# 02_POWER.net
KiCad netlist of a schematic drawn in Altium Designer
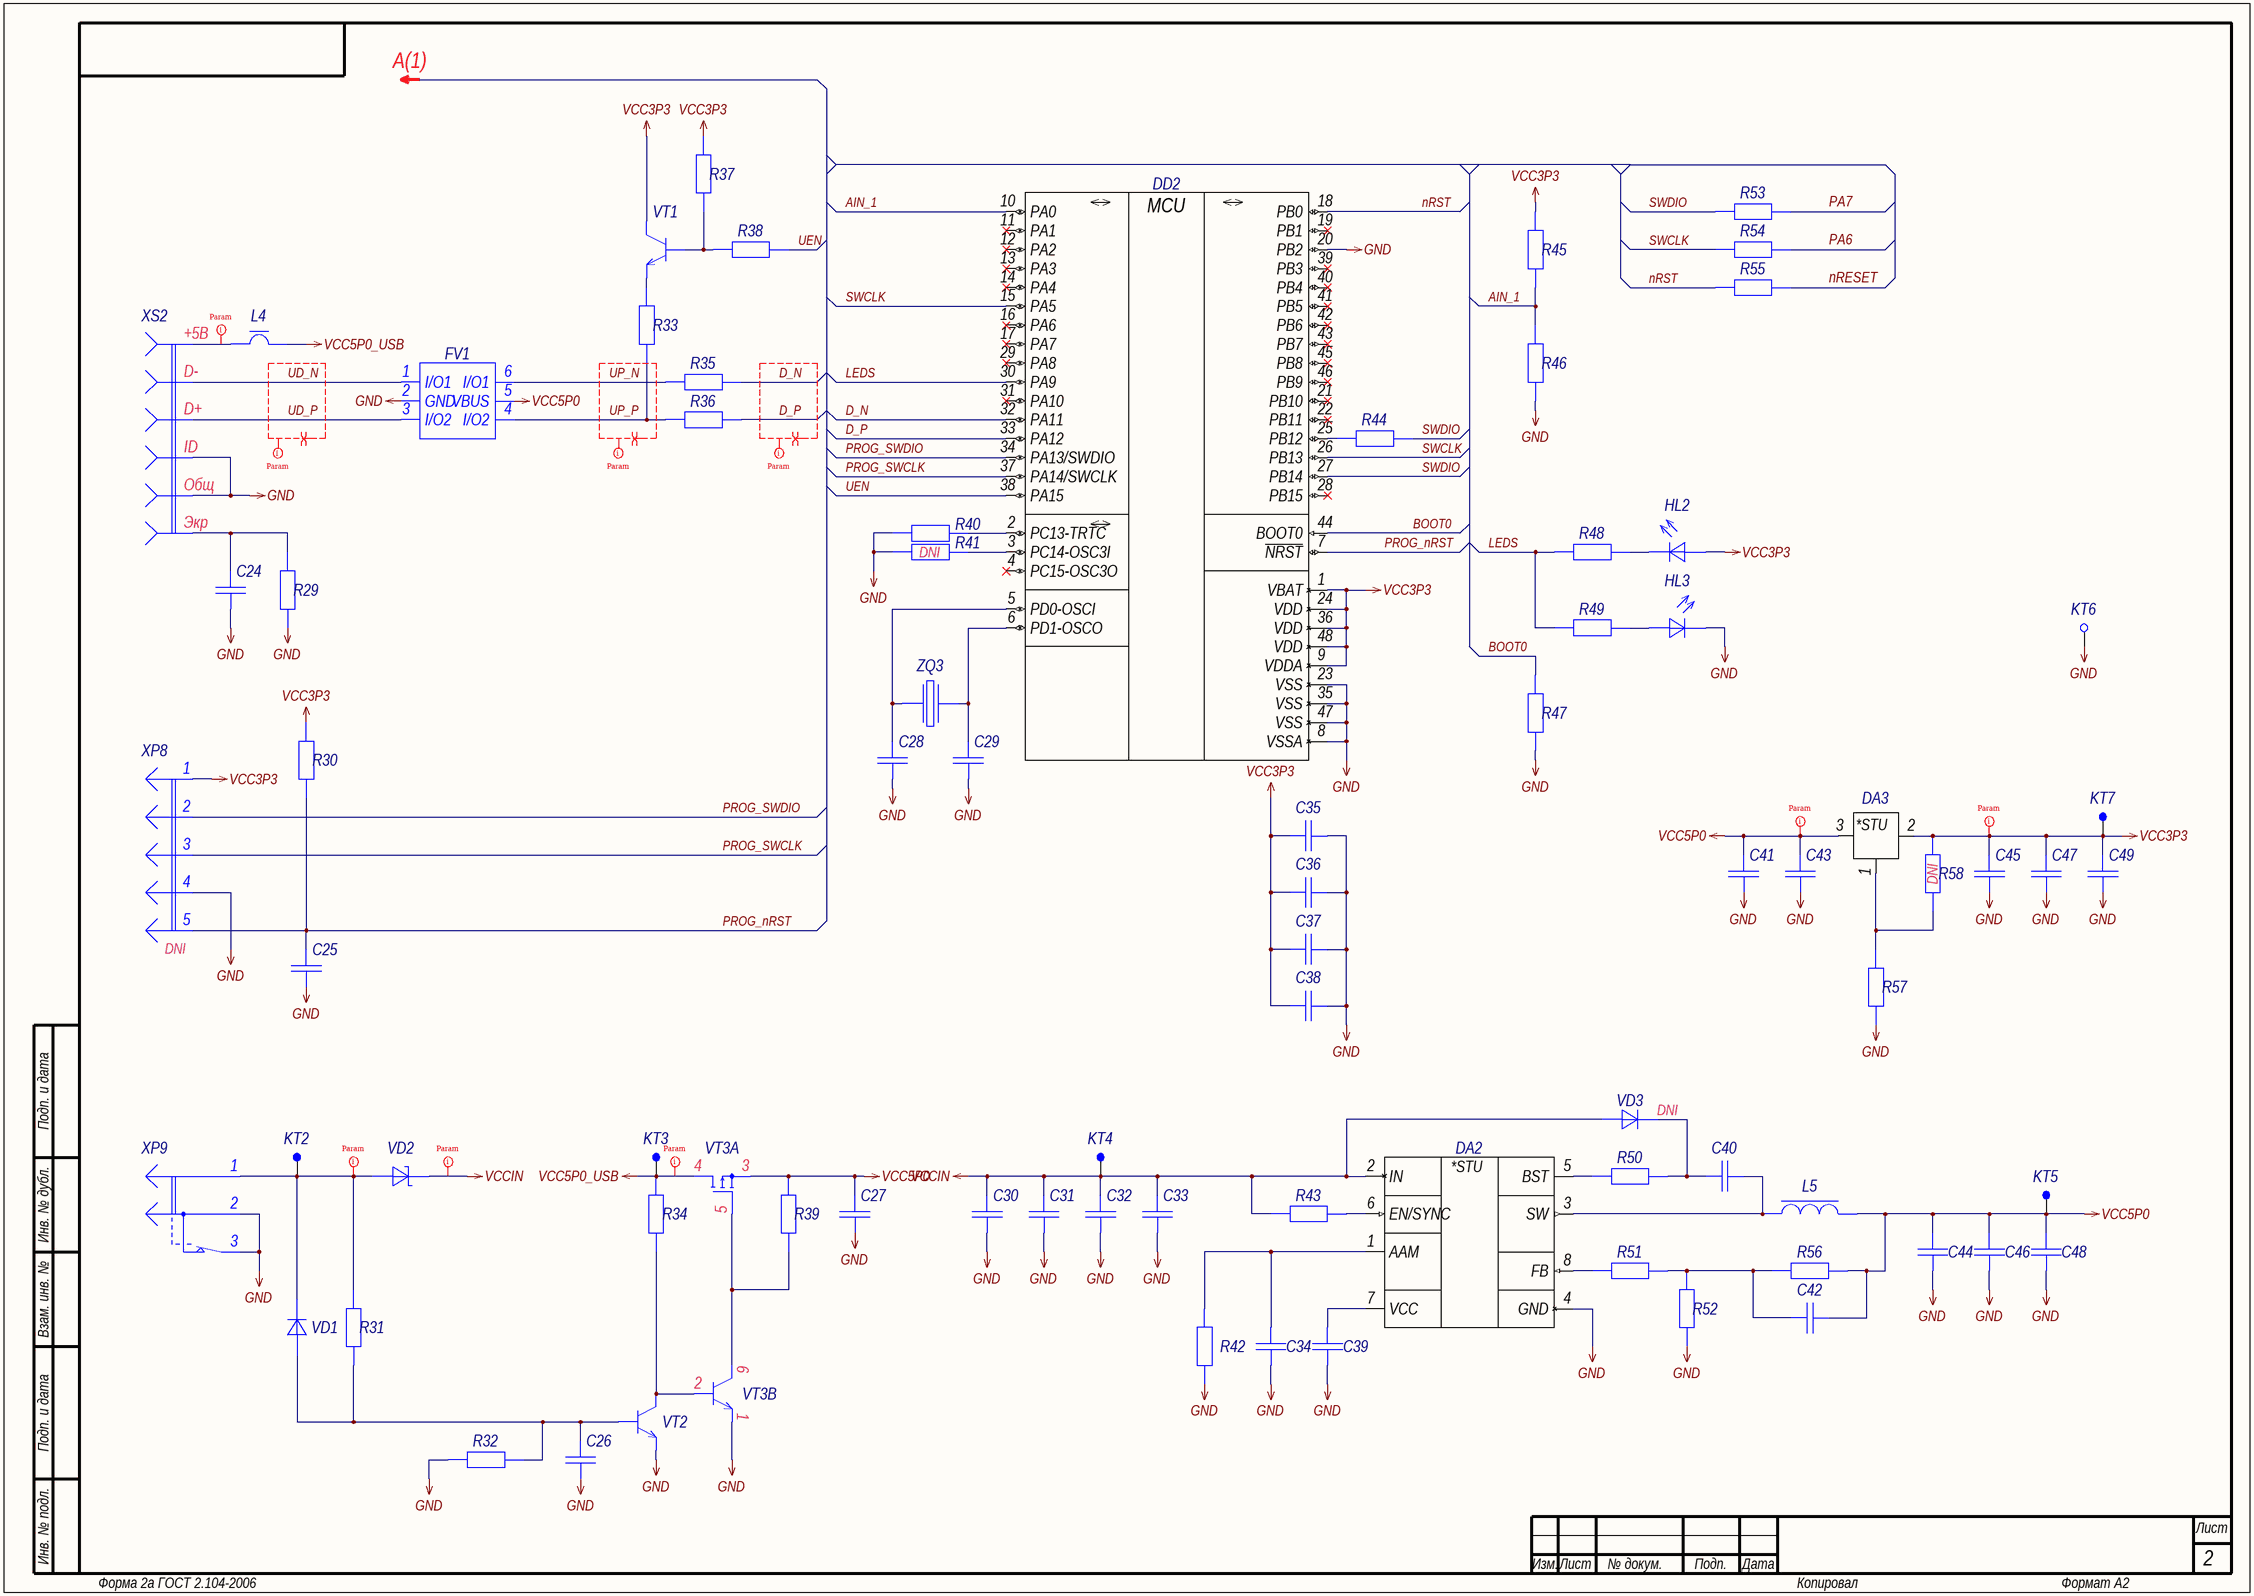
[diagram p0: 02_POWER.SchDoc]

(export (version "E")
  (design (tool "Eeschema 10.0.6"))
  (components
    (comp (ref "C24")
      (value "Capacitor")
      (footprint "C0603_L")
      (fields
        (field (name "PART NUMBER") "GRM188R72A104KA35D")
        (field (name "VOLTAGE") "100V")
        (field (name "TOLERANCE") "±10%")
        (field (name "PUBLISHER") "Andrew Danich")
      )
      (libsource (lib "ADLib") (part "Capacitor"))
    )
    (comp (ref "C25")
      (value "Capacitor")
      (footprint "C0603_L")
      (fields
        (field (name "PART NUMBER") "GRM188R72A104KA35D")
        (field (name "VOLTAGE") "100V")
        (field (name "TOLERANCE") "±10%")
        (field (name "PUBLISHER") "Andrew Danich")
      )
      (libsource (lib "ADLib") (part "Capacitor"))
    )
    (comp (ref "C26")
      (value "Capacitor")
      (footprint "C0603_L")
      (fields
        (field (name "PART NUMBER") "GRM188R72A104KA35D")
        (field (name "VOLTAGE") "100V")
        (field (name "TOLERANCE") "±10%")
        (field (name "PUBLISHER") "Andrew Danich")
      )
      (libsource (lib "ADLib") (part "Capacitor"))
    )
    (comp (ref "C27")
      (value "Capacitor")
      (footprint "C0805_L")
      (fields
        (field (name "PART NUMBER") "GRM21BR60J226ME39L")
        (field (name "VOLTAGE") "6.3V")
        (field (name "TOLERANCE") "±20%")
        (field (name "PUBLISHER") "Andrew Danich")
      )
      (libsource (lib "ADLib") (part "Capacitor"))
    )
    (comp (ref "C28")
      (value "Capacitor")
      (footprint "C0603_L")
      (fields
        (field (name "PART NUMBER") "GCM1885C1H150JA16D")
        (field (name "VOLTAGE") "50V")
        (field (name "TOLERANCE") "±5%")
        (field (name "PUBLISHER") "Andrew Danich")
      )
      (libsource (lib "ADLib") (part "Capacitor"))
    )
    (comp (ref "C29")
      (value "Capacitor")
      (footprint "C0603_L")
      (fields
        (field (name "PART NUMBER") "GCM1885C1H150JA16D")
        (field (name "VOLTAGE") "50V")
        (field (name "TOLERANCE") "±5%")
        (field (name "PUBLISHER") "Andrew Danich")
      )
      (libsource (lib "ADLib") (part "Capacitor"))
    )
    (comp (ref "C30")
      (value "Capacitor")
      (footprint "C1206_L")
      (fields
        (field (name "PART NUMBER") "GRM31CR71A226KE15L")
        (field (name "VOLTAGE") "10V")
        (field (name "TOLERANCE") "±10%")
        (field (name "PUBLISHER") "Andrew Danich")
      )
      (libsource (lib "ADLib") (part "Capacitor"))
    )
    (comp (ref "C31")
      (value "Capacitor")
      (footprint "C1206_L")
      (fields
        (field (name "PART NUMBER") "GRM31CR71A226KE15L")
        (field (name "VOLTAGE") "10V")
        (field (name "TOLERANCE") "±10%")
        (field (name "PUBLISHER") "Andrew Danich")
      )
      (libsource (lib "ADLib") (part "Capacitor"))
    )
    (comp (ref "C32")
      (value "Capacitor")
      (footprint "C1206_L")
      (fields
        (field (name "PART NUMBER") "GRM31CR71A226KE15L")
        (field (name "VOLTAGE") "10V")
        (field (name "TOLERANCE") "±10%")
        (field (name "PUBLISHER") "Andrew Danich")
      )
      (libsource (lib "ADLib") (part "Capacitor"))
    )
    (comp (ref "C33")
      (value "Capacitor")
      (footprint "C0603_L")
      (fields
        (field (name "PART NUMBER") "GRM188R72A104KA35D")
        (field (name "VOLTAGE") "100V")
        (field (name "TOLERANCE") "±10%")
        (field (name "PUBLISHER") "Andrew Danich")
      )
      (libsource (lib "ADLib") (part "Capacitor"))
    )
    (comp (ref "C34")
      (value "Capacitor")
      (footprint "C0603_L")
      (fields
        (field (name "PART NUMBER") "GRM1885C2A102JA01D")
        (field (name "VOLTAGE") "100V")
        (field (name "TOLERANCE") "±5%")
        (field (name "PUBLISHER") "Andrew Danich")
      )
      (libsource (lib "ADLib") (part "Capacitor"))
    )
    (comp (ref "C35")
      (value "Capacitor")
      (footprint "C0603_L")
      (fields
        (field (name "PART NUMBER") "GRM188R72A104KA35D")
        (field (name "VOLTAGE") "100V")
        (field (name "TOLERANCE") "±10%")
        (field (name "PUBLISHER") "Andrew Danich")
      )
      (libsource (lib "ADLib") (part "Capacitor"))
    )
    (comp (ref "C36")
      (value "Capacitor")
      (footprint "C0603_L")
      (fields
        (field (name "PART NUMBER") "GRM188R72A104KA35D")
        (field (name "VOLTAGE") "100V")
        (field (name "TOLERANCE") "±10%")
        (field (name "PUBLISHER") "Andrew Danich")
      )
      (libsource (lib "ADLib") (part "Capacitor"))
    )
    (comp (ref "C37")
      (value "Capacitor")
      (footprint "C0603_L")
      (fields
        (field (name "PART NUMBER") "GRM188R72A104KA35D")
        (field (name "VOLTAGE") "100V")
        (field (name "TOLERANCE") "±10%")
        (field (name "PUBLISHER") "Andrew Danich")
      )
      (libsource (lib "ADLib") (part "Capacitor"))
    )
    (comp (ref "C38")
      (value "Capacitor")
      (footprint "C0603_L")
      (fields
        (field (name "PART NUMBER") "GRM188R72A104KA35D")
        (field (name "VOLTAGE") "100V")
        (field (name "TOLERANCE") "±10%")
        (field (name "PUBLISHER") "Andrew Danich")
      )
      (libsource (lib "ADLib") (part "Capacitor"))
    )
    (comp (ref "C39")
      (value "Capacitor")
      (footprint "C0603_L")
      (fields
        (field (name "PART NUMBER") "GRM188R72A104KA35D")
        (field (name "VOLTAGE") "100V")
        (field (name "TOLERANCE") "±10%")
        (field (name "PUBLISHER") "Andrew Danich")
      )
      (libsource (lib "ADLib") (part "Capacitor"))
    )
    (comp (ref "C40")
      (value "Capacitor")
      (footprint "C0603_L")
      (fields
        (field (name "PART NUMBER") "GRM188R72A104KA35D")
        (field (name "VOLTAGE") "100V")
        (field (name "TOLERANCE") "±10%")
        (field (name "PUBLISHER") "Andrew Danich")
      )
      (libsource (lib "ADLib") (part "Capacitor"))
    )
    (comp (ref "C41")
      (value "Capacitor")
      (footprint "C0805_L")
      (fields
        (field (name "PART NUMBER") "GRM21BR60J226ME39L")
        (field (name "VOLTAGE") "6.3V")
        (field (name "TOLERANCE") "±20%")
        (field (name "PUBLISHER") "Andrew Danich")
      )
      (libsource (lib "ADLib") (part "Capacitor"))
    )
    (comp (ref "C42")
      (value "Capacitor")
      (footprint "C0603_L")
      (fields
        (field (name "PART NUMBER") "GRM1885C1H330JA01D")
        (field (name "VOLTAGE") "50V")
        (field (name "TOLERANCE") "±5%")
        (field (name "PUBLISHER") "Andrew Danich")
      )
      (libsource (lib "ADLib") (part "Capacitor"))
    )
    (comp (ref "C43")
      (value "Capacitor")
      (footprint "C0603_L")
      (fields
        (field (name "PART NUMBER") "GRM188R72A104KA35D")
        (field (name "VOLTAGE") "100V")
        (field (name "TOLERANCE") "±10%")
        (field (name "PUBLISHER") "Andrew Danich")
      )
      (libsource (lib "ADLib") (part "Capacitor"))
    )
    (comp (ref "C44")
      (value "Capacitor")
      (footprint "C0805_L")
      (fields
        (field (name "PART NUMBER") "GRM21BR60J226ME39L")
        (field (name "VOLTAGE") "6.3V")
        (field (name "TOLERANCE") "±20%")
        (field (name "PUBLISHER") "Andrew Danich")
      )
      (libsource (lib "ADLib") (part "Capacitor"))
    )
    (comp (ref "C45")
      (value "Capacitor")
      (footprint "C0603_L")
      (fields
        (field (name "PART NUMBER") "GRM188R72A104KA35D")
        (field (name "VOLTAGE") "100V")
        (field (name "TOLERANCE") "±10%")
        (field (name "PUBLISHER") "Andrew Danich")
      )
      (libsource (lib "ADLib") (part "Capacitor"))
    )
    (comp (ref "C46")
      (value "Capacitor")
      (footprint "C0805_L")
      (fields
        (field (name "PART NUMBER") "GRM21BR60J226ME39L")
        (field (name "VOLTAGE") "6.3V")
        (field (name "TOLERANCE") "±20%")
        (field (name "PUBLISHER") "Andrew Danich")
      )
      (libsource (lib "ADLib") (part "Capacitor"))
    )
    (comp (ref "C47")
      (value "Capacitor")
      (footprint "C0805_L")
      (fields
        (field (name "PART NUMBER") "GRM21BR60J226ME39L")
        (field (name "VOLTAGE") "6.3V")
        (field (name "TOLERANCE") "±20%")
        (field (name "PUBLISHER") "Andrew Danich")
      )
      (libsource (lib "ADLib") (part "Capacitor"))
    )
    (comp (ref "C48")
      (value "Capacitor")
      (footprint "C0805_L")
      (fields
        (field (name "PART NUMBER") "GRM21BR60J226ME39L")
        (field (name "VOLTAGE") "6.3V")
        (field (name "TOLERANCE") "±20%")
        (field (name "PUBLISHER") "Andrew Danich")
      )
      (libsource (lib "ADLib") (part "Capacitor"))
    )
    (comp (ref "C49")
      (value "Capacitor")
      (footprint "C0805_L")
      (fields
        (field (name "PART NUMBER") "GRM21BR60J226ME39L")
        (field (name "VOLTAGE") "6.3V")
        (field (name "TOLERANCE") "±20%")
        (field (name "PUBLISHER") "Andrew Danich")
      )
      (libsource (lib "ADLib") (part "Capacitor"))
    )
    (comp (ref "DA2")
      (value "MP2315GJ")
      (footprint "TSOT-23-8_065P290X160X100_N")
      (fields
        (field (name "PART NUMBER") "MP2315GJ-Z")
        (field (name "MANUFACTURER") "Monolithic Power Systems")
        (field (name "PUBLISHER") "Andrew Danich")
      )
      (libsource (lib "ADLib") (part "MP2315GJ"))
    )
    (comp (ref "DA3")
      (value "LM1117-Series")
      (footprint "SOT-223_230P650X350X180_N")
      (fields (field (name "PART NUMBER") "LM1117MPX-3.3") (field (name "PUBLISHER") "Andrew Danich"))
      (libsource (lib "ADLib") (part "LM1117-Series"))
    )
    (comp (ref "DD2")
      (value "STM32F103Cxxx-Series")
      (footprint "LQFP-48_050P700X700X160_N")
      (fields
        (field (name "PART NUMBER") "STM32F103C8T6")
        (field (name "MANUFACTURER") "STMicroelectronics")
        (field (name "PUBLISHER") "Andrew Danich")
      )
      (libsource (lib "ADLib") (part "STM32F103Cxxx-Series"))
    )
    (comp (ref "FV1")
      (value "USBLC6-2SC6")
      (footprint "SOT-23-6_095P290X160X145_N")
      (fields (field (name "MANUFACTURER") "STMicroelectronics") (field (name "PUBLISHER") "Andrew Danich"))
      (libsource (lib "ADLib") (part "USBLC6-2SC6"))
    )
    (comp (ref "HL2")
      (value "Text")
      (footprint "LD0603_L")
      (fields (field (name "PART NUMBER") "BL-LS0603GC") (field (name "PUBLISHER") "Andrew Danich"))
      (libsource (lib "ADLib") (part "Led-1"))
    )
    (comp (ref "HL3")
      (value "Text")
      (footprint "LD0603_L")
      (fields (field (name "PART NUMBER") "BL-LS0603HC") (field (name "PUBLISHER") "Andrew Danich"))
      (libsource (lib "ADLib") (part "Led-1"))
    )
    (comp (ref "KT2")
      (value "VCCIN")
      (footprint "TP-SMT-C-0.8mm")
      (fields (field (name "PART NUMBER") "TestPoint-SMT") (field (name "PUBLISHER") "Andrew Danich"))
      (libsource (lib "ADLib") (part "TP-S-1"))
    )
    (comp (ref "KT3")
      (value "VBUS")
      (footprint "TP-SMT-C-0.8mm")
      (fields (field (name "PART NUMBER") "TestPoint-SMT") (field (name "PUBLISHER") "Andrew Danich"))
      (libsource (lib "ADLib") (part "TP-S-1"))
    )
    (comp (ref "KT4")
      (value "VCCIN")
      (footprint "TP-SMT-C-0.8mm")
      (fields (field (name "PART NUMBER") "TestPoint-SMT") (field (name "PUBLISHER") "Andrew Danich"))
      (libsource (lib "ADLib") (part "TP-S-1"))
    )
    (comp (ref "KT5")
      (value "+5V")
      (footprint "TP-SMT-C-0.8mm")
      (fields (field (name "PART NUMBER") "TestPoint-SMT") (field (name "PUBLISHER") "Andrew Danich"))
      (libsource (lib "ADLib") (part "TP-S-1"))
    )
    (comp (ref "KT6")
      (value "ОБЩ")
      (footprint "5001")
      (fields
        (field (name "PART NUMBER") "5001")
        (field (name "MANUFACTURER") "Keystone Electronics")
        (field (name "PUBLISHER") "Andrew Danich")
      )
      (libsource (lib "ADLib") (part "TP-1"))
    )
    (comp (ref "KT7")
      (value "+3.3V")
      (footprint "TP-SMT-C-0.8mm")
      (fields (field (name "PART NUMBER") "TestPoint-SMT") (field (name "PUBLISHER") "Andrew Danich"))
      (libsource (lib "ADLib") (part "TP-S-1"))
    )
    (comp (ref "L4")
      (value "FerriteBead")
      (footprint "L0603_L")
      (fields
        (field (name "PART NUMBER") "BLM18PG331SN1")
        (field (name "TOLERANCE") "±25%")
        (field (name "MANUFACTURER") "Murata")
        (field (name "PUBLISHER") "Andrew Danich")
      )
      (libsource (lib "ADLib") (part "FerriteBead"))
    )
    (comp (ref "L5")
      (value "Coil")
      (footprint "SRP5030T-Series")
      (fields
        (field (name "PART NUMBER") "SRP5030T-4R7M")
        (field (name "TOLERANCE") "±20%")
        (field (name "MANUFACTURER") "Bourns")
        (field (name "PUBLISHER") "Andrew Danich")
      )
      (libsource (lib "ADLib") (part "Coil"))
    )
    (comp (ref "R29")
      (value "Resistor")
      (footprint "R0603_L")
      (fields
        (field (name "PART NUMBER") "RC0603JR-071ML")
        (field (name "TOLERANCE") "±5%")
        (field (name "MANUFACTURER") "Yageo")
        (field (name "PUBLISHER") "Andrew Danich")
      )
      (libsource (lib "ADLib") (part "Resistor"))
    )
    (comp (ref "R30")
      (value "Resistor")
      (footprint "R0603_L")
      (fields
        (field (name "PART NUMBER") "RC0603JR-0710KL")
        (field (name "TOLERANCE") "±5%")
        (field (name "MANUFACTURER") "Yageo")
        (field (name "PUBLISHER") "Andrew Danich")
      )
      (libsource (lib "ADLib") (part "Resistor"))
    )
    (comp (ref "R31")
      (value "Resistor")
      (footprint "R0603_L")
      (fields
        (field (name "PART NUMBER") "RC0603JR-0710KL")
        (field (name "TOLERANCE") "±5%")
        (field (name "MANUFACTURER") "Yageo")
        (field (name "PUBLISHER") "Andrew Danich")
      )
      (libsource (lib "ADLib") (part "Resistor"))
    )
    (comp (ref "R32")
      (value "Resistor")
      (footprint "R0603_L")
      (fields
        (field (name "PART NUMBER") "RC0603JR-0710KL")
        (field (name "TOLERANCE") "±5%")
        (field (name "MANUFACTURER") "Yageo")
        (field (name "PUBLISHER") "Andrew Danich")
      )
      (libsource (lib "ADLib") (part "Resistor"))
    )
    (comp (ref "R33")
      (value "Resistor")
      (footprint "R0603_L")
      (fields
        (field (name "PART NUMBER") "RC0603JR-071K5L")
        (field (name "TOLERANCE") "±5%")
        (field (name "MANUFACTURER") "Yageo")
        (field (name "PUBLISHER") "Andrew Danich")
      )
      (libsource (lib "ADLib") (part "Resistor"))
    )
    (comp (ref "R34")
      (value "Resistor")
      (footprint "R0603_L")
      (fields
        (field (name "PART NUMBER") "RC0603JR-0710KL")
        (field (name "TOLERANCE") "±5%")
        (field (name "MANUFACTURER") "Yageo")
        (field (name "PUBLISHER") "Andrew Danich")
      )
      (libsource (lib "ADLib") (part "Resistor"))
    )
    (comp (ref "R35")
      (value "Resistor")
      (footprint "R0603_L")
      (fields
        (field (name "PART NUMBER") "RC0603JR-0722RL")
        (field (name "TOLERANCE") "±5%")
        (field (name "MANUFACTURER") "Yageo")
        (field (name "PUBLISHER") "Andrew Danich")
      )
      (libsource (lib "ADLib") (part "Resistor"))
    )
    (comp (ref "R36")
      (value "Resistor")
      (footprint "R0603_L")
      (fields
        (field (name "PART NUMBER") "RC0603JR-0722RL")
        (field (name "TOLERANCE") "±5%")
        (field (name "MANUFACTURER") "Yageo")
        (field (name "PUBLISHER") "Andrew Danich")
      )
      (libsource (lib "ADLib") (part "Resistor"))
    )
    (comp (ref "R37")
      (value "Resistor")
      (footprint "R0603_L")
      (fields
        (field (name "PART NUMBER") "RC0603JR-074K7L")
        (field (name "TOLERANCE") "±5%")
        (field (name "MANUFACTURER") "Yageo")
        (field (name "PUBLISHER") "Andrew Danich")
      )
      (libsource (lib "ADLib") (part "Resistor"))
    )
    (comp (ref "R38")
      (value "Resistor")
      (footprint "R0603_L")
      (fields
        (field (name "PART NUMBER") "RC0603JR-07100R")
        (field (name "TOLERANCE") "±5%")
        (field (name "MANUFACTURER") "Yageo")
        (field (name "PUBLISHER") "Andrew Danich")
      )
      (libsource (lib "ADLib") (part "Resistor"))
    )
    (comp (ref "R39")
      (value "Resistor")
      (footprint "R0603_L")
      (fields
        (field (name "PART NUMBER") "RC0603JR-0710KL")
        (field (name "TOLERANCE") "±5%")
        (field (name "MANUFACTURER") "Yageo")
        (field (name "PUBLISHER") "Andrew Danich")
      )
      (libsource (lib "ADLib") (part "Resistor"))
    )
    (comp (ref "R40")
      (value "Resistor")
      (footprint "R0603_L")
      (fields
        (field (name "PART NUMBER") "RC0603JR-0710KL")
        (field (name "TOLERANCE") "±5%")
        (field (name "MANUFACTURER") "Yageo")
        (field (name "PUBLISHER") "Andrew Danich")
      )
      (libsource (lib "ADLib") (part "Resistor"))
    )
    (comp (ref "R41")
      (value "Resistor")
      (footprint "R0603_L")
      (fields
        (field (name "PART NUMBER") "RC0603JR-0710KL")
        (field (name "TOLERANCE") "±5%")
        (field (name "MANUFACTURER") "Yageo")
        (field (name "PUBLISHER") "Andrew Danich")
      )
      (libsource (lib "ADLib") (part "Resistor"))
    )
    (comp (ref "R42")
      (value "Resistor")
      (footprint "R0603_L")
      (fields
        (field (name "PART NUMBER") "RC0603FR-0763K4L")
        (field (name "TOLERANCE") "±1%")
        (field (name "MANUFACTURER") "Yageo")
        (field (name "PUBLISHER") "Andrew Danich")
      )
      (libsource (lib "ADLib") (part "Resistor"))
    )
    (comp (ref "R43")
      (value "Resistor")
      (footprint "R0603_L")
      (fields
        (field (name "PART NUMBER") "RC0603JR-07100KL")
        (field (name "TOLERANCE") "±5%")
        (field (name "MANUFACTURER") "Yageo")
        (field (name "PUBLISHER") "Andrew Danich")
      )
      (libsource (lib "ADLib") (part "Resistor"))
    )
    (comp (ref "R44")
      (value "Resistor")
      (footprint "R0603_L")
      (fields
        (field (name "PART NUMBER") "RC0603JR-07100R")
        (field (name "TOLERANCE") "±5%")
        (field (name "MANUFACTURER") "Yageo")
        (field (name "PUBLISHER") "Andrew Danich")
      )
      (libsource (lib "ADLib") (part "Resistor"))
    )
    (comp (ref "R45")
      (value "Resistor")
      (footprint "R0603_L")
      (fields
        (field (name "PART NUMBER") "RC0603JR-074K7L")
        (field (name "TOLERANCE") "±5%")
        (field (name "MANUFACTURER") "Yageo")
        (field (name "PUBLISHER") "Andrew Danich")
      )
      (libsource (lib "ADLib") (part "Resistor"))
    )
    (comp (ref "R46")
      (value "Resistor")
      (footprint "R0603_L")
      (fields
        (field (name "PART NUMBER") "RC0603JR-074K7L")
        (field (name "TOLERANCE") "±5%")
        (field (name "MANUFACTURER") "Yageo")
        (field (name "PUBLISHER") "Andrew Danich")
      )
      (libsource (lib "ADLib") (part "Resistor"))
    )
    (comp (ref "R47")
      (value "Resistor")
      (footprint "R0603_L")
      (fields
        (field (name "PART NUMBER") "RC0603JR-0710KL")
        (field (name "TOLERANCE") "±5%")
        (field (name "MANUFACTURER") "Yageo")
        (field (name "PUBLISHER") "Andrew Danich")
      )
      (libsource (lib "ADLib") (part "Resistor"))
    )
    (comp (ref "R48")
      (value "Resistor")
      (footprint "R0603_L")
      (fields
        (field (name "PART NUMBER") "RC0603JR-07330RL")
        (field (name "TOLERANCE") "±5%")
        (field (name "MANUFACTURER") "Yageo")
        (field (name "PUBLISHER") "Andrew Danich")
      )
      (libsource (lib "ADLib") (part "Resistor"))
    )
    (comp (ref "R49")
      (value "Resistor")
      (footprint "R0603_L")
      (fields
        (field (name "PART NUMBER") "RC0603JR-07330RL")
        (field (name "TOLERANCE") "±5%")
        (field (name "MANUFACTURER") "Yageo")
        (field (name "PUBLISHER") "Andrew Danich")
      )
      (libsource (lib "ADLib") (part "Resistor"))
    )
    (comp (ref "R50")
      (value "Resistor")
      (footprint "R0603_L")
      (fields
        (field (name "PART NUMBER") "RC0603JR-0720RL")
        (field (name "TOLERANCE") "±5%")
        (field (name "MANUFACTURER") "Yageo")
        (field (name "PUBLISHER") "Andrew Danich")
      )
      (libsource (lib "ADLib") (part "Resistor"))
    )
    (comp (ref "R51")
      (value "Resistor")
      (footprint "R0603_L")
      (fields
        (field (name "PART NUMBER") "RC0603JR-0733KL")
        (field (name "TOLERANCE") "±5%")
        (field (name "MANUFACTURER") "Yageo")
        (field (name "PUBLISHER") "Andrew Danich")
      )
      (libsource (lib "ADLib") (part "Resistor"))
    )
    (comp (ref "R52")
      (value "Resistor")
      (footprint "R0603_L")
      (fields
        (field (name "PART NUMBER") "RC0603JR-076K8L")
        (field (name "TOLERANCE") "±5%")
        (field (name "MANUFACTURER") "Yageo")
        (field (name "PUBLISHER") "Andrew Danich")
      )
      (libsource (lib "ADLib") (part "Resistor"))
    )
    (comp (ref "R53")
      (value "Resistor")
      (footprint "R0603_L")
      (fields
        (field (name "PART NUMBER") "RC0603JR-0722RL")
        (field (name "TOLERANCE") "±5%")
        (field (name "MANUFACTURER") "Yageo")
        (field (name "PUBLISHER") "Andrew Danich")
      )
      (libsource (lib "ADLib") (part "Resistor"))
    )
    (comp (ref "R54")
      (value "Resistor")
      (footprint "R0603_L")
      (fields
        (field (name "PART NUMBER") "RC0603JR-0722RL")
        (field (name "TOLERANCE") "±5%")
        (field (name "MANUFACTURER") "Yageo")
        (field (name "PUBLISHER") "Andrew Danich")
      )
      (libsource (lib "ADLib") (part "Resistor"))
    )
    (comp (ref "R55")
      (value "Resistor")
      (footprint "R0603_L")
      (fields
        (field (name "PART NUMBER") "RC0603JR-0722RL")
        (field (name "TOLERANCE") "±5%")
        (field (name "MANUFACTURER") "Yageo")
        (field (name "PUBLISHER") "Andrew Danich")
      )
      (libsource (lib "ADLib") (part "Resistor"))
    )
    (comp (ref "R56")
      (value "Resistor")
      (footprint "R0603_L")
      (fields
        (field (name "PART NUMBER") "RC0603JR-0736KL")
        (field (name "TOLERANCE") "±5%")
        (field (name "MANUFACTURER") "Yageo")
        (field (name "PUBLISHER") "Andrew Danich")
      )
      (libsource (lib "ADLib") (part "Resistor"))
    )
    (comp (ref "R57")
      (value "Resistor")
      (footprint "R0603_L")
      (fields
        (field (name "PART NUMBER") "RC0603JR-070R")
        (field (name "TOLERANCE") "±5%")
        (field (name "MANUFACTURER") "Yageo")
        (field (name "PUBLISHER") "Andrew Danich")
      )
      (libsource (lib "ADLib") (part "Resistor"))
    )
    (comp (ref "R58")
      (value "Resistor")
      (footprint "R0603_L")
      (fields
        (field (name "PART NUMBER") "RC0603JR-070R")
        (field (name "TOLERANCE") "±5%")
        (field (name "MANUFACTURER") "Yageo")
        (field (name "PUBLISHER") "Andrew Danich")
      )
      (libsource (lib "ADLib") (part "Resistor"))
    )
    (comp (ref "VD1")
      (value "Diode")
      (footprint "SOD-323")
      (fields
        (field (name "PART NUMBER") "1N4148WS-7-F")
        (field (name "MANUFACTURER") "Diodes Incorporated")
        (field (name "PUBLISHER") "Andrew Danich")
      )
      (libsource (lib "ADLib") (part "Diode"))
    )
    (comp (ref "VD2")
      (value "Schottky")
      (footprint "SOD-123")
      (fields
        (field (name "PART NUMBER") "MBR0540T1G")
        (field (name "MANUFACTURER") "ON Semiconductor")
        (field (name "PUBLISHER") "Andrew Danich")
      )
      (libsource (lib "ADLib") (part "Schottky"))
    )
    (comp (ref "VD3")
      (value "Diode")
      (footprint "SOD-323")
      (fields
        (field (name "PART NUMBER") "1N4148WS-7-F")
        (field (name "MANUFACTURER") "Diodes Incorporated")
        (field (name "PUBLISHER") "Andrew Danich")
      )
      (libsource (lib "ADLib") (part "Diode"))
    )
    (comp (ref "VT1")
      (value "BJT-NPN")
      (footprint "SOT-23_190P290X160X145_N")
      (fields (field (name "PART NUMBER") "BC847") (field (name "PUBLISHER") "Andrew Danich"))
      (libsource (lib "ADLib") (part "BJT-NPN"))
    )
    (comp (ref "VT2")
      (value "BJT-NPN")
      (footprint "SOT-23_190P290X160X145_N")
      (fields (field (name "PART NUMBER") "BC847") (field (name "PUBLISHER") "Andrew Danich"))
      (libsource (lib "ADLib") (part "BJT-NPN"))
    )
    (comp (ref "VT3")
      (value "PMC85XP")
      (footprint "SOT-1118-2M_065P200X200X065_N")
      (fields (field (name "MANUFACTURER") "NXP Semiconductors") (field (name "PUBLISHER") "Andrew Danich"))
      (libsource (lib "ADLib") (part "PMC85XP"))
    )
    (comp (ref "XP8")
      (value "Prog")
      (footprint "PLS-5")
      (fields (field (name "PART NUMBER") "PLS-5") (field (name "PUBLISHER") "Andrew Danich"))
      (libsource (lib "ADLib") (part "Con-5-M"))
    )
    (comp (ref "XP9")
      (value "DC")
      (footprint "DJK-02-Series")
      (fields
        (field (name "PART NUMBER") "DJK-02A")
        (field (name "MANUFACTURER") "JIA YI")
        (field (name "PUBLISHER") "Andrew Danich")
      )
      (libsource (lib "ADLib") (part "Con-2-M-DP"))
    )
    (comp (ref "XS2")
      (value "J-Link")
      (footprint "1981568-1")
      (fields
        (field (name "PART NUMBER") "1981568-1")
        (field (name "MANUFACTURER") "TE Connectivity")
        (field (name "PUBLISHER") "Andrew Danich")
      )
      (libsource (lib "ADLib") (part "Con-6-F-USB"))
    )
    (comp (ref "ZQ3")
      (value "Crystal")
      (footprint "SMD 5x3.2mm")
      (fields
        (field (name "PART NUMBER") "KX-9A 8.0 MHz 30/50/100 16 pF")
        (field (name "MANUFACTURER") "Geyer")
        (field (name "PUBLISHER") "Andrew Danich")
      )
      (libsource (lib "ADLib") (part "Crystal"))
    )
  )
  (nets
    (net (code "1") (name "/AIN_1") (class "Default")
      (node (ref "DD2") (pin "10") (pinfunction "PA0_10") (pintype "bidirectional"))
      (node (ref "R45") (pin "1") (pinfunction "1_1") (pintype "passive"))
      (node (ref "R46") (pin "2") (pinfunction "2_2") (pintype "passive"))
    )
    (net (code "2") (name "/BOOT0") (class "Default")
      (node (ref "DD2") (pin "44") (pinfunction "BOOT0_44") (pintype "input"))
      (node (ref "R47") (pin "2") (pinfunction "2_2") (pintype "passive"))
    )
    (net (code "3") (name "/D_N") (class "Default")
      (node (ref "DD2") (pin "32") (pinfunction "PA11_32") (pintype "bidirectional"))
      (node (ref "R35") (pin "2") (pinfunction "2_2") (pintype "passive"))
    )
    (net (code "4") (name "/D_P") (class "Default")
      (node (ref "DD2") (pin "33") (pinfunction "PA12_33") (pintype "bidirectional"))
      (node (ref "R36") (pin "2") (pinfunction "2_2") (pintype "passive"))
    )
    (net (code "5") (name "/LEDS") (class "Default")
      (node (ref "DD2") (pin "30") (pinfunction "PA9_30") (pintype "bidirectional"))
      (node (ref "R48") (pin "1") (pinfunction "1_1") (pintype "passive"))
      (node (ref "R49") (pin "1") (pinfunction "1_1") (pintype "passive"))
    )
    (net (code "6") (name "/PA6") (class "Default")
      (node (ref "R54") (pin "2") (pinfunction "2_2") (pintype "passive"))
    )
    (net (code "7") (name "/PA7") (class "Default")
      (node (ref "R53") (pin "2") (pinfunction "2_2") (pintype "passive"))
    )
    (net (code "8") (name "/PROG_SWCLK") (class "Default")
      (node (ref "DD2") (pin "37") (pinfunction "PA14/SWCLK_37") (pintype "bidirectional"))
      (node (ref "XP8") (pin "3") (pintype "passive"))
    )
    (net (code "9") (name "/PROG_SWDIO") (class "Default")
      (node (ref "DD2") (pin "34") (pinfunction "PA13/SWDIO_34") (pintype "bidirectional"))
      (node (ref "XP8") (pin "2") (pintype "passive"))
    )
    (net (code "10") (name "/PROG_nRST") (class "Default")
      (node (ref "C25") (pin "2") (pinfunction "2_2") (pintype "passive"))
      (node (ref "DD2") (pin "7") (pinfunction "~{NRST}_7") (pintype "bidirectional"))
      (node (ref "R30") (pin "1") (pinfunction "1_1") (pintype "passive"))
      (node (ref "XP8") (pin "5") (pintype "passive"))
    )
    (net (code "11") (name "/SWCLK") (class "Default")
      (node (ref "DD2") (pin "15") (pinfunction "PA5_15") (pintype "bidirectional"))
      (node (ref "DD2") (pin "26") (pinfunction "PB13_26") (pintype "bidirectional"))
      (node (ref "R54") (pin "1") (pinfunction "1_1") (pintype "passive"))
    )
    (net (code "12") (name "/SWDIO") (class "Default")
      (node (ref "DD2") (pin "27") (pinfunction "PB14_27") (pintype "bidirectional"))
      (node (ref "R44") (pin "2") (pinfunction "2_2") (pintype "passive"))
      (node (ref "R53") (pin "1") (pinfunction "1_1") (pintype "passive"))
    )
    (net (code "13") (name "/UD_N") (class "Default")
      (node (ref "FV1") (pin "1") (pinfunction "I/O1_1") (pintype "passive"))
      (node (ref "XS2") (pin "2") (pintype "passive"))
    )
    (net (code "14") (name "/UD_P") (class "Default")
      (node (ref "FV1") (pin "3") (pinfunction "I/O2_3") (pintype "passive"))
      (node (ref "XS2") (pin "3") (pintype "passive"))
    )
    (net (code "15") (name "/UEN") (class "Default")
      (node (ref "DD2") (pin "38") (pinfunction "PA15_38") (pintype "bidirectional"))
      (node (ref "R38") (pin "2") (pinfunction "2_2") (pintype "passive"))
    )
    (net (code "16") (name "/UP_N") (class "Default")
      (node (ref "FV1") (pin "6") (pinfunction "I/O1_6") (pintype "passive"))
      (node (ref "R35") (pin "1") (pinfunction "1_1") (pintype "passive"))
    )
    (net (code "17") (name "/UP_P") (class "Default")
      (node (ref "FV1") (pin "4") (pinfunction "I/O2_4") (pintype "passive"))
      (node (ref "R33") (pin "1") (pinfunction "1_1") (pintype "passive"))
      (node (ref "R36") (pin "1") (pinfunction "1_1") (pintype "passive"))
    )
    (net (code "18") (name "/nRESET") (class "Default")
      (node (ref "R55") (pin "2") (pinfunction "2_2") (pintype "passive"))
    )
    (net (code "19") (name "/nRST") (class "Default")
      (node (ref "DD2") (pin "18") (pinfunction "PB0_18") (pintype "bidirectional"))
      (node (ref "R55") (pin "1") (pinfunction "1_1") (pintype "passive"))
    )
    (net (code "20") (name "GND") (class "Default")
      (node (ref "C24") (pin "1") (pinfunction "1_1") (pintype "passive"))
      (node (ref "C25") (pin "1") (pinfunction "1_1") (pintype "passive"))
      (node (ref "C26") (pin "1") (pinfunction "1_1") (pintype "passive"))
      (node (ref "C27") (pin "1") (pinfunction "1_1") (pintype "passive"))
      (node (ref "C28") (pin "1") (pinfunction "1_1") (pintype "passive"))
      (node (ref "C29") (pin "1") (pinfunction "1_1") (pintype "passive"))
      (node (ref "C30") (pin "1") (pinfunction "1_1") (pintype "passive"))
      (node (ref "C31") (pin "1") (pinfunction "1_1") (pintype "passive"))
      (node (ref "C32") (pin "1") (pinfunction "1_1") (pintype "passive"))
      (node (ref "C33") (pin "1") (pinfunction "1_1") (pintype "passive"))
      (node (ref "C34") (pin "1") (pinfunction "1_1") (pintype "passive"))
      (node (ref "C35") (pin "1") (pinfunction "1_1") (pintype "passive"))
      (node (ref "C36") (pin "1") (pinfunction "1_1") (pintype "passive"))
      (node (ref "C37") (pin "1") (pinfunction "1_1") (pintype "passive"))
      (node (ref "C38") (pin "1") (pinfunction "1_1") (pintype "passive"))
      (node (ref "C39") (pin "1") (pinfunction "1_1") (pintype "passive"))
      (node (ref "C41") (pin "1") (pinfunction "1_1") (pintype "passive"))
      (node (ref "C43") (pin "1") (pinfunction "1_1") (pintype "passive"))
      (node (ref "C44") (pin "1") (pinfunction "1_1") (pintype "passive"))
      (node (ref "C45") (pin "1") (pinfunction "1_1") (pintype "passive"))
      (node (ref "C46") (pin "1") (pinfunction "1_1") (pintype "passive"))
      (node (ref "C47") (pin "1") (pinfunction "1_1") (pintype "passive"))
      (node (ref "C48") (pin "1") (pinfunction "1_1") (pintype "passive"))
      (node (ref "C49") (pin "1") (pinfunction "1_1") (pintype "passive"))
      (node (ref "DA2") (pin "4") (pinfunction "GND_4") (pintype "power_in"))
      (node (ref "DD2") (pin "20") (pinfunction "PB2_20") (pintype "bidirectional"))
      (node (ref "DD2") (pin "23") (pinfunction "VSS_23") (pintype "power_in"))
      (node (ref "DD2") (pin "35") (pinfunction "VSS_35") (pintype "power_in"))
      (node (ref "DD2") (pin "47") (pinfunction "VSS_47") (pintype "power_in"))
      (node (ref "DD2") (pin "8") (pinfunction "VSSA_8") (pintype "power_in"))
      (node (ref "FV1") (pin "2") (pinfunction "GND_2") (pintype "passive"))
      (node (ref "HL3") (pin "2") (pinfunction "К_2") (pintype "passive"))
      (node (ref "KT6") (pin "1") (pinfunction "1_1") (pintype "passive"))
      (node (ref "R29") (pin "1") (pinfunction "1_1") (pintype "passive"))
      (node (ref "R32") (pin "2") (pinfunction "2_2") (pintype "passive"))
      (node (ref "R40") (pin "2") (pinfunction "2_2") (pintype "passive"))
      (node (ref "R41") (pin "2") (pinfunction "2_2") (pintype "passive"))
      (node (ref "R42") (pin "1") (pinfunction "1_1") (pintype "passive"))
      (node (ref "R46") (pin "1") (pinfunction "1_1") (pintype "passive"))
      (node (ref "R47") (pin "1") (pinfunction "1_1") (pintype "passive"))
      (node (ref "R52") (pin "1") (pinfunction "1_1") (pintype "passive"))
      (node (ref "R57") (pin "1") (pinfunction "1_1") (pintype "passive"))
      (node (ref "VT2") (pin "3") (pinfunction "Э_3") (pintype "passive"))
      (node (ref "VT3") (pin "1") (pinfunction "Э_1") (pintype "passive"))
      (node (ref "XP8") (pin "4") (pintype "passive"))
      (node (ref "XP9") (pin "2") (pintype "passive"))
      (node (ref "XP9") (pin "3") (pintype "passive"))
      (node (ref "XS2") (pin "4") (pintype "passive"))
      (node (ref "XS2") (pin "5") (pintype "passive"))
    )
    (net (code "21") (name "Net-(C24-Pad2)") (class "Default")
      (node (ref "C24") (pin "2") (pinfunction "2_2") (pintype "passive"))
      (node (ref "R29") (pin "2") (pinfunction "2_2") (pintype "passive"))
      (node (ref "XS2") (pin "6") (pintype "passive"))
    )
    (net (code "22") (name "Net-(C42-Pad1)") (class "Default")
      (node (ref "C42") (pin "1") (pinfunction "1_1") (pintype "passive"))
      (node (ref "R51") (pin "2") (pinfunction "2_2") (pintype "passive"))
      (node (ref "R52") (pin "2") (pinfunction "2_2") (pintype "passive"))
      (node (ref "R56") (pin "1") (pinfunction "1_1") (pintype "passive"))
    )
    (net (code "23") (name "Net-(DA2-AAM)") (class "Default")
      (node (ref "C34") (pin "2") (pinfunction "2_2") (pintype "passive"))
      (node (ref "DA2") (pin "1") (pinfunction "AAM_1") (pintype "passive"))
      (node (ref "R42") (pin "2") (pinfunction "2_2") (pintype "passive"))
    )
    (net (code "24") (name "Net-(DA2-BST)") (class "Default")
      (node (ref "DA2") (pin "5") (pinfunction "BST_5") (pintype "passive"))
      (node (ref "R50") (pin "1") (pinfunction "1_1") (pintype "passive"))
    )
    (net (code "25") (name "Net-(DA2-EN{slash}SYNC)") (class "Default")
      (node (ref "DA2") (pin "6") (pinfunction "EN/SYNC_6") (pintype "input"))
      (node (ref "R43") (pin "2") (pinfunction "2_2") (pintype "passive"))
    )
    (net (code "26") (name "Net-(DA2-FB)") (class "Default")
      (node (ref "DA2") (pin "8") (pinfunction "FB_8") (pintype "input"))
      (node (ref "R51") (pin "1") (pinfunction "1_1") (pintype "passive"))
    )
    (net (code "27") (name "Net-(DA2-SW)") (class "Default")
      (node (ref "C40") (pin "2") (pinfunction "2_2") (pintype "passive"))
      (node (ref "DA2") (pin "3") (pinfunction "SW_3") (pintype "output"))
      (node (ref "L5") (pin "1") (pinfunction "1_1") (pintype "passive"))
    )
    (net (code "28") (name "Net-(DA2-VCC)") (class "Default")
      (node (ref "C39") (pin "2") (pinfunction "2_2") (pintype "passive"))
      (node (ref "DA2") (pin "7") (pinfunction "VCC_7") (pintype "power_in"))
    )
    (net (code "29") (name "Net-(DA3-Adj{slash}GND)") (class "Default")
      (node (ref "DA3") (pin "1") (pinfunction "Adj/GND_1") (pintype "passive"))
      (node (ref "R57") (pin "2") (pinfunction "2_2") (pintype "passive"))
      (node (ref "R58") (pin "1") (pinfunction "1_1") (pintype "passive"))
    )
    (net (code "30") (name "Net-(DD2-PB12)") (class "Default")
      (node (ref "DD2") (pin "25") (pinfunction "PB12_25") (pintype "bidirectional"))
      (node (ref "R44") (pin "1") (pinfunction "1_1") (pintype "passive"))
    )
    (net (code "31") (name "Net-(DD2-PC13-TRTC)") (class "Default")
      (node (ref "DD2") (pin "2") (pinfunction "PC13-TRTC_2") (pintype "bidirectional"))
      (node (ref "R40") (pin "1") (pinfunction "1_1") (pintype "passive"))
    )
    (net (code "32") (name "Net-(DD2-PC14-OSC3I)") (class "Default")
      (node (ref "DD2") (pin "3") (pinfunction "PC14-OSC3I_3") (pintype "bidirectional"))
      (node (ref "R41") (pin "1") (pinfunction "1_1") (pintype "passive"))
    )
    (net (code "33") (name "Net-(DD2-PD0-OSCI)") (class "Default")
      (node (ref "C28") (pin "2") (pinfunction "2_2") (pintype "passive"))
      (node (ref "DD2") (pin "5") (pinfunction "PD0-OSCI_5") (pintype "bidirectional"))
      (node (ref "ZQ3") (pin "3") (pinfunction "3_3") (pintype "passive"))
    )
    (net (code "34") (name "Net-(DD2-PD1-OSCO)") (class "Default")
      (node (ref "C29") (pin "2") (pinfunction "2_2") (pintype "passive"))
      (node (ref "DD2") (pin "6") (pinfunction "PD1-OSCO_6") (pintype "bidirectional"))
      (node (ref "ZQ3") (pin "1") (pinfunction "1_1") (pintype "passive"))
    )
    (net (code "35") (name "Net-(HL2-К)") (class "Default")
      (node (ref "HL2") (pin "2") (pinfunction "К_2") (pintype "passive"))
      (node (ref "R48") (pin "2") (pinfunction "2_2") (pintype "passive"))
    )
    (net (code "36") (name "Net-(HL3-А)") (class "Default")
      (node (ref "HL3") (pin "1") (pinfunction "А_1") (pintype "passive"))
      (node (ref "R49") (pin "2") (pinfunction "2_2") (pintype "passive"))
    )
    (net (code "37") (name "Net-(L4-Pad1)") (class "Default")
      (node (ref "L4") (pin "1") (pinfunction "1_1") (pintype "passive"))
      (node (ref "XS2") (pin "1") (pintype "passive"))
    )
    (net (code "38") (name "Net-(VD1-А)") (class "Default")
      (node (ref "C26") (pin "2") (pinfunction "2_2") (pintype "passive"))
      (node (ref "R31") (pin "1") (pinfunction "1_1") (pintype "passive"))
      (node (ref "R32") (pin "1") (pinfunction "1_1") (pintype "passive"))
      (node (ref "VD1") (pin "1") (pinfunction "А_1") (pintype "passive"))
      (node (ref "VT2") (pin "1") (pinfunction "Б_1") (pintype "passive"))
    )
    (net (code "39") (name "Net-(VD1-К)") (class "Default")
      (node (ref "KT2") (pin "1") (pinfunction "1_1") (pintype "passive"))
      (node (ref "R31") (pin "2") (pinfunction "2_2") (pintype "passive"))
      (node (ref "VD1") (pin "2") (pinfunction "К_2") (pintype "passive"))
      (node (ref "VD2") (pin "1") (pinfunction "А_1") (pintype "passive"))
      (node (ref "XP9") (pin "1") (pintype "passive"))
    )
    (net (code "40") (name "Net-(VD3-К)") (class "Default")
      (node (ref "C40") (pin "1") (pinfunction "1_1") (pintype "passive"))
      (node (ref "R50") (pin "2") (pinfunction "2_2") (pintype "passive"))
      (node (ref "VD3") (pin "2") (pinfunction "К_2") (pintype "passive"))
    )
    (net (code "41") (name "Net-(VT1-Б)") (class "Default")
      (node (ref "R37") (pin "1") (pinfunction "1_1") (pintype "passive"))
      (node (ref "R38") (pin "1") (pinfunction "1_1") (pintype "passive"))
      (node (ref "VT1") (pin "1") (pinfunction "Б_1") (pintype "passive"))
    )
    (net (code "42") (name "Net-(VT1-Э)") (class "Default")
      (node (ref "R33") (pin "2") (pinfunction "2_2") (pintype "passive"))
      (node (ref "VT1") (pin "3") (pinfunction "Э_3") (pintype "passive"))
    )
    (net (code "43") (name "Net-(VT2-К)") (class "Default")
      (node (ref "R34") (pin "1") (pinfunction "1_1") (pintype "passive"))
      (node (ref "VT2") (pin "2") (pinfunction "К_2") (pintype "passive"))
      (node (ref "VT3") (pin "2") (pinfunction "Б_2") (pintype "passive"))
    )
    (net (code "44") (name "Net-(VT3A-G)") (class "Default")
      (node (ref "R39") (pin "1") (pinfunction "1_1") (pintype "passive"))
      (node (ref "VT3") (pin "5") (pinfunction "G_5") (pintype "passive"))
      (node (ref "VT3") (pin "6") (pinfunction "К_6") (pintype "passive"))
    )
    (net (code "45") (name "VCC3P3") (class "Default")
      (node (ref "C35") (pin "2") (pinfunction "2_2") (pintype "passive"))
      (node (ref "C36") (pin "2") (pinfunction "2_2") (pintype "passive"))
      (node (ref "C37") (pin "2") (pinfunction "2_2") (pintype "passive"))
      (node (ref "C38") (pin "2") (pinfunction "2_2") (pintype "passive"))
      (node (ref "C45") (pin "2") (pinfunction "2_2") (pintype "passive"))
      (node (ref "C47") (pin "2") (pinfunction "2_2") (pintype "passive"))
      (node (ref "C49") (pin "2") (pinfunction "2_2") (pintype "passive"))
      (node (ref "DA3") (pin "2") (pinfunction "Out_2") (pintype "passive"))
      (node (ref "DD2") (pin "1") (pinfunction "VBAT_1") (pintype "power_in"))
      (node (ref "DD2") (pin "24") (pinfunction "VDD_24") (pintype "power_in"))
      (node (ref "DD2") (pin "36") (pinfunction "VDD_36") (pintype "power_in"))
      (node (ref "DD2") (pin "48") (pinfunction "VDD_48") (pintype "power_in"))
      (node (ref "DD2") (pin "9") (pinfunction "VDDA_9") (pintype "power_in"))
      (node (ref "HL2") (pin "1") (pinfunction "А_1") (pintype "passive"))
      (node (ref "KT7") (pin "1") (pinfunction "1_1") (pintype "passive"))
      (node (ref "R30") (pin "2") (pinfunction "2_2") (pintype "passive"))
      (node (ref "R37") (pin "2") (pinfunction "2_2") (pintype "passive"))
      (node (ref "R45") (pin "2") (pinfunction "2_2") (pintype "passive"))
      (node (ref "R58") (pin "2") (pinfunction "2_2") (pintype "passive"))
      (node (ref "VT1") (pin "2") (pinfunction "К_2") (pintype "passive"))
      (node (ref "XP8") (pin "1") (pintype "passive"))
    )
    (net (code "46") (name "VCC5P0") (class "Default")
      (node (ref "C27") (pin "2") (pinfunction "2_2") (pintype "passive"))
      (node (ref "C41") (pin "2") (pinfunction "2_2") (pintype "passive"))
      (node (ref "C42") (pin "2") (pinfunction "2_2") (pintype "passive"))
      (node (ref "C43") (pin "2") (pinfunction "2_2") (pintype "passive"))
      (node (ref "C44") (pin "2") (pinfunction "2_2") (pintype "passive"))
      (node (ref "C46") (pin "2") (pinfunction "2_2") (pintype "passive"))
      (node (ref "C48") (pin "2") (pinfunction "2_2") (pintype "passive"))
      (node (ref "DA3") (pin "3") (pinfunction "In_3") (pintype "passive"))
      (node (ref "FV1") (pin "5") (pinfunction "VBUS_5") (pintype "passive"))
      (node (ref "KT5") (pin "1") (pinfunction "1_1") (pintype "passive"))
      (node (ref "L5") (pin "2") (pinfunction "2_2") (pintype "passive"))
      (node (ref "R39") (pin "2") (pinfunction "2_2") (pintype "passive"))
      (node (ref "R56") (pin "2") (pinfunction "2_2") (pintype "passive"))
      (node (ref "VT3") (pin "3") (pinfunction "S_3") (pintype "passive"))
    )
    (net (code "47") (name "VCC5P0_USB") (class "Default")
      (node (ref "KT3") (pin "1") (pinfunction "1_1") (pintype "passive"))
      (node (ref "L4") (pin "2") (pinfunction "2_2") (pintype "passive"))
      (node (ref "R34") (pin "2") (pinfunction "2_2") (pintype "passive"))
      (node (ref "VT3") (pin "4") (pinfunction "D_4") (pintype "passive"))
    )
    (net (code "48") (name "VCCIN") (class "Default")
      (node (ref "C30") (pin "2") (pinfunction "2_2") (pintype "passive"))
      (node (ref "C31") (pin "2") (pinfunction "2_2") (pintype "passive"))
      (node (ref "C32") (pin "2") (pinfunction "2_2") (pintype "passive"))
      (node (ref "C33") (pin "2") (pinfunction "2_2") (pintype "passive"))
      (node (ref "DA2") (pin "2") (pinfunction "IN_2") (pintype "power_in"))
      (node (ref "KT4") (pin "1") (pinfunction "1_1") (pintype "passive"))
      (node (ref "R43") (pin "1") (pinfunction "1_1") (pintype "passive"))
      (node (ref "VD2") (pin "2") (pinfunction "К_2") (pintype "passive"))
      (node (ref "VD3") (pin "1") (pinfunction "А_1") (pintype "passive"))
    )
    (net (code "49") (name "unconnected-(DD2-PA1-Pad11)") (class "Default")
      (node (ref "DD2") (pin "11") (pinfunction "PA1_11") (pintype "bidirectional+no_connect"))
    )
    (net (code "50") (name "unconnected-(DD2-PA2-Pad12)") (class "Default")
      (node (ref "DD2") (pin "12") (pinfunction "PA2_12") (pintype "bidirectional+no_connect"))
    )
    (net (code "51") (name "unconnected-(DD2-PA3-Pad13)") (class "Default")
      (node (ref "DD2") (pin "13") (pinfunction "PA3_13") (pintype "bidirectional+no_connect"))
    )
    (net (code "52") (name "unconnected-(DD2-PA4-Pad14)") (class "Default")
      (node (ref "DD2") (pin "14") (pinfunction "PA4_14") (pintype "bidirectional+no_connect"))
    )
    (net (code "53") (name "unconnected-(DD2-PA6-Pad16)") (class "Default")
      (node (ref "DD2") (pin "16") (pinfunction "PA6_16") (pintype "bidirectional+no_connect"))
    )
    (net (code "54") (name "unconnected-(DD2-PA7-Pad17)") (class "Default")
      (node (ref "DD2") (pin "17") (pinfunction "PA7_17") (pintype "bidirectional+no_connect"))
    )
    (net (code "55") (name "unconnected-(DD2-PA8-Pad29)") (class "Default")
      (node (ref "DD2") (pin "29") (pinfunction "PA8_29") (pintype "bidirectional+no_connect"))
    )
    (net (code "56") (name "unconnected-(DD2-PA10-Pad31)") (class "Default")
      (node (ref "DD2") (pin "31") (pinfunction "PA10_31") (pintype "bidirectional+no_connect"))
    )
    (net (code "57") (name "unconnected-(DD2-PB1-Pad19)") (class "Default")
      (node (ref "DD2") (pin "19") (pinfunction "PB1_19") (pintype "bidirectional+no_connect"))
    )
    (net (code "58") (name "unconnected-(DD2-PB3-Pad39)") (class "Default")
      (node (ref "DD2") (pin "39") (pinfunction "PB3_39") (pintype "bidirectional+no_connect"))
    )
    (net (code "59") (name "unconnected-(DD2-PB4-Pad40)") (class "Default")
      (node (ref "DD2") (pin "40") (pinfunction "PB4_40") (pintype "bidirectional+no_connect"))
    )
    (net (code "60") (name "unconnected-(DD2-PB5-Pad41)") (class "Default")
      (node (ref "DD2") (pin "41") (pinfunction "PB5_41") (pintype "bidirectional+no_connect"))
    )
    (net (code "61") (name "unconnected-(DD2-PB6-Pad42)") (class "Default")
      (node (ref "DD2") (pin "42") (pinfunction "PB6_42") (pintype "bidirectional+no_connect"))
    )
    (net (code "62") (name "unconnected-(DD2-PB7-Pad43)") (class "Default")
      (node (ref "DD2") (pin "43") (pinfunction "PB7_43") (pintype "bidirectional+no_connect"))
    )
    (net (code "63") (name "unconnected-(DD2-PB8-Pad45)") (class "Default")
      (node (ref "DD2") (pin "45") (pinfunction "PB8_45") (pintype "bidirectional+no_connect"))
    )
    (net (code "64") (name "unconnected-(DD2-PB9-Pad46)") (class "Default")
      (node (ref "DD2") (pin "46") (pinfunction "PB9_46") (pintype "bidirectional+no_connect"))
    )
    (net (code "65") (name "unconnected-(DD2-PB10-Pad21)") (class "Default")
      (node (ref "DD2") (pin "21") (pinfunction "PB10_21") (pintype "bidirectional+no_connect"))
    )
    (net (code "66") (name "unconnected-(DD2-PB11-Pad22)") (class "Default")
      (node (ref "DD2") (pin "22") (pinfunction "PB11_22") (pintype "bidirectional+no_connect"))
    )
    (net (code "67") (name "unconnected-(DD2-PB15-Pad28)") (class "Default")
      (node (ref "DD2") (pin "28") (pinfunction "PB15_28") (pintype "bidirectional+no_connect"))
    )
    (net (code "68") (name "unconnected-(DD2-PC15-OSC3O-Pad4)") (class "Default")
      (node (ref "DD2") (pin "4") (pinfunction "PC15-OSC3O_4") (pintype "bidirectional+no_connect"))
    )
  )
)
